# luxer.net
KiCad netlist of a schematic drawn in EasyEDA
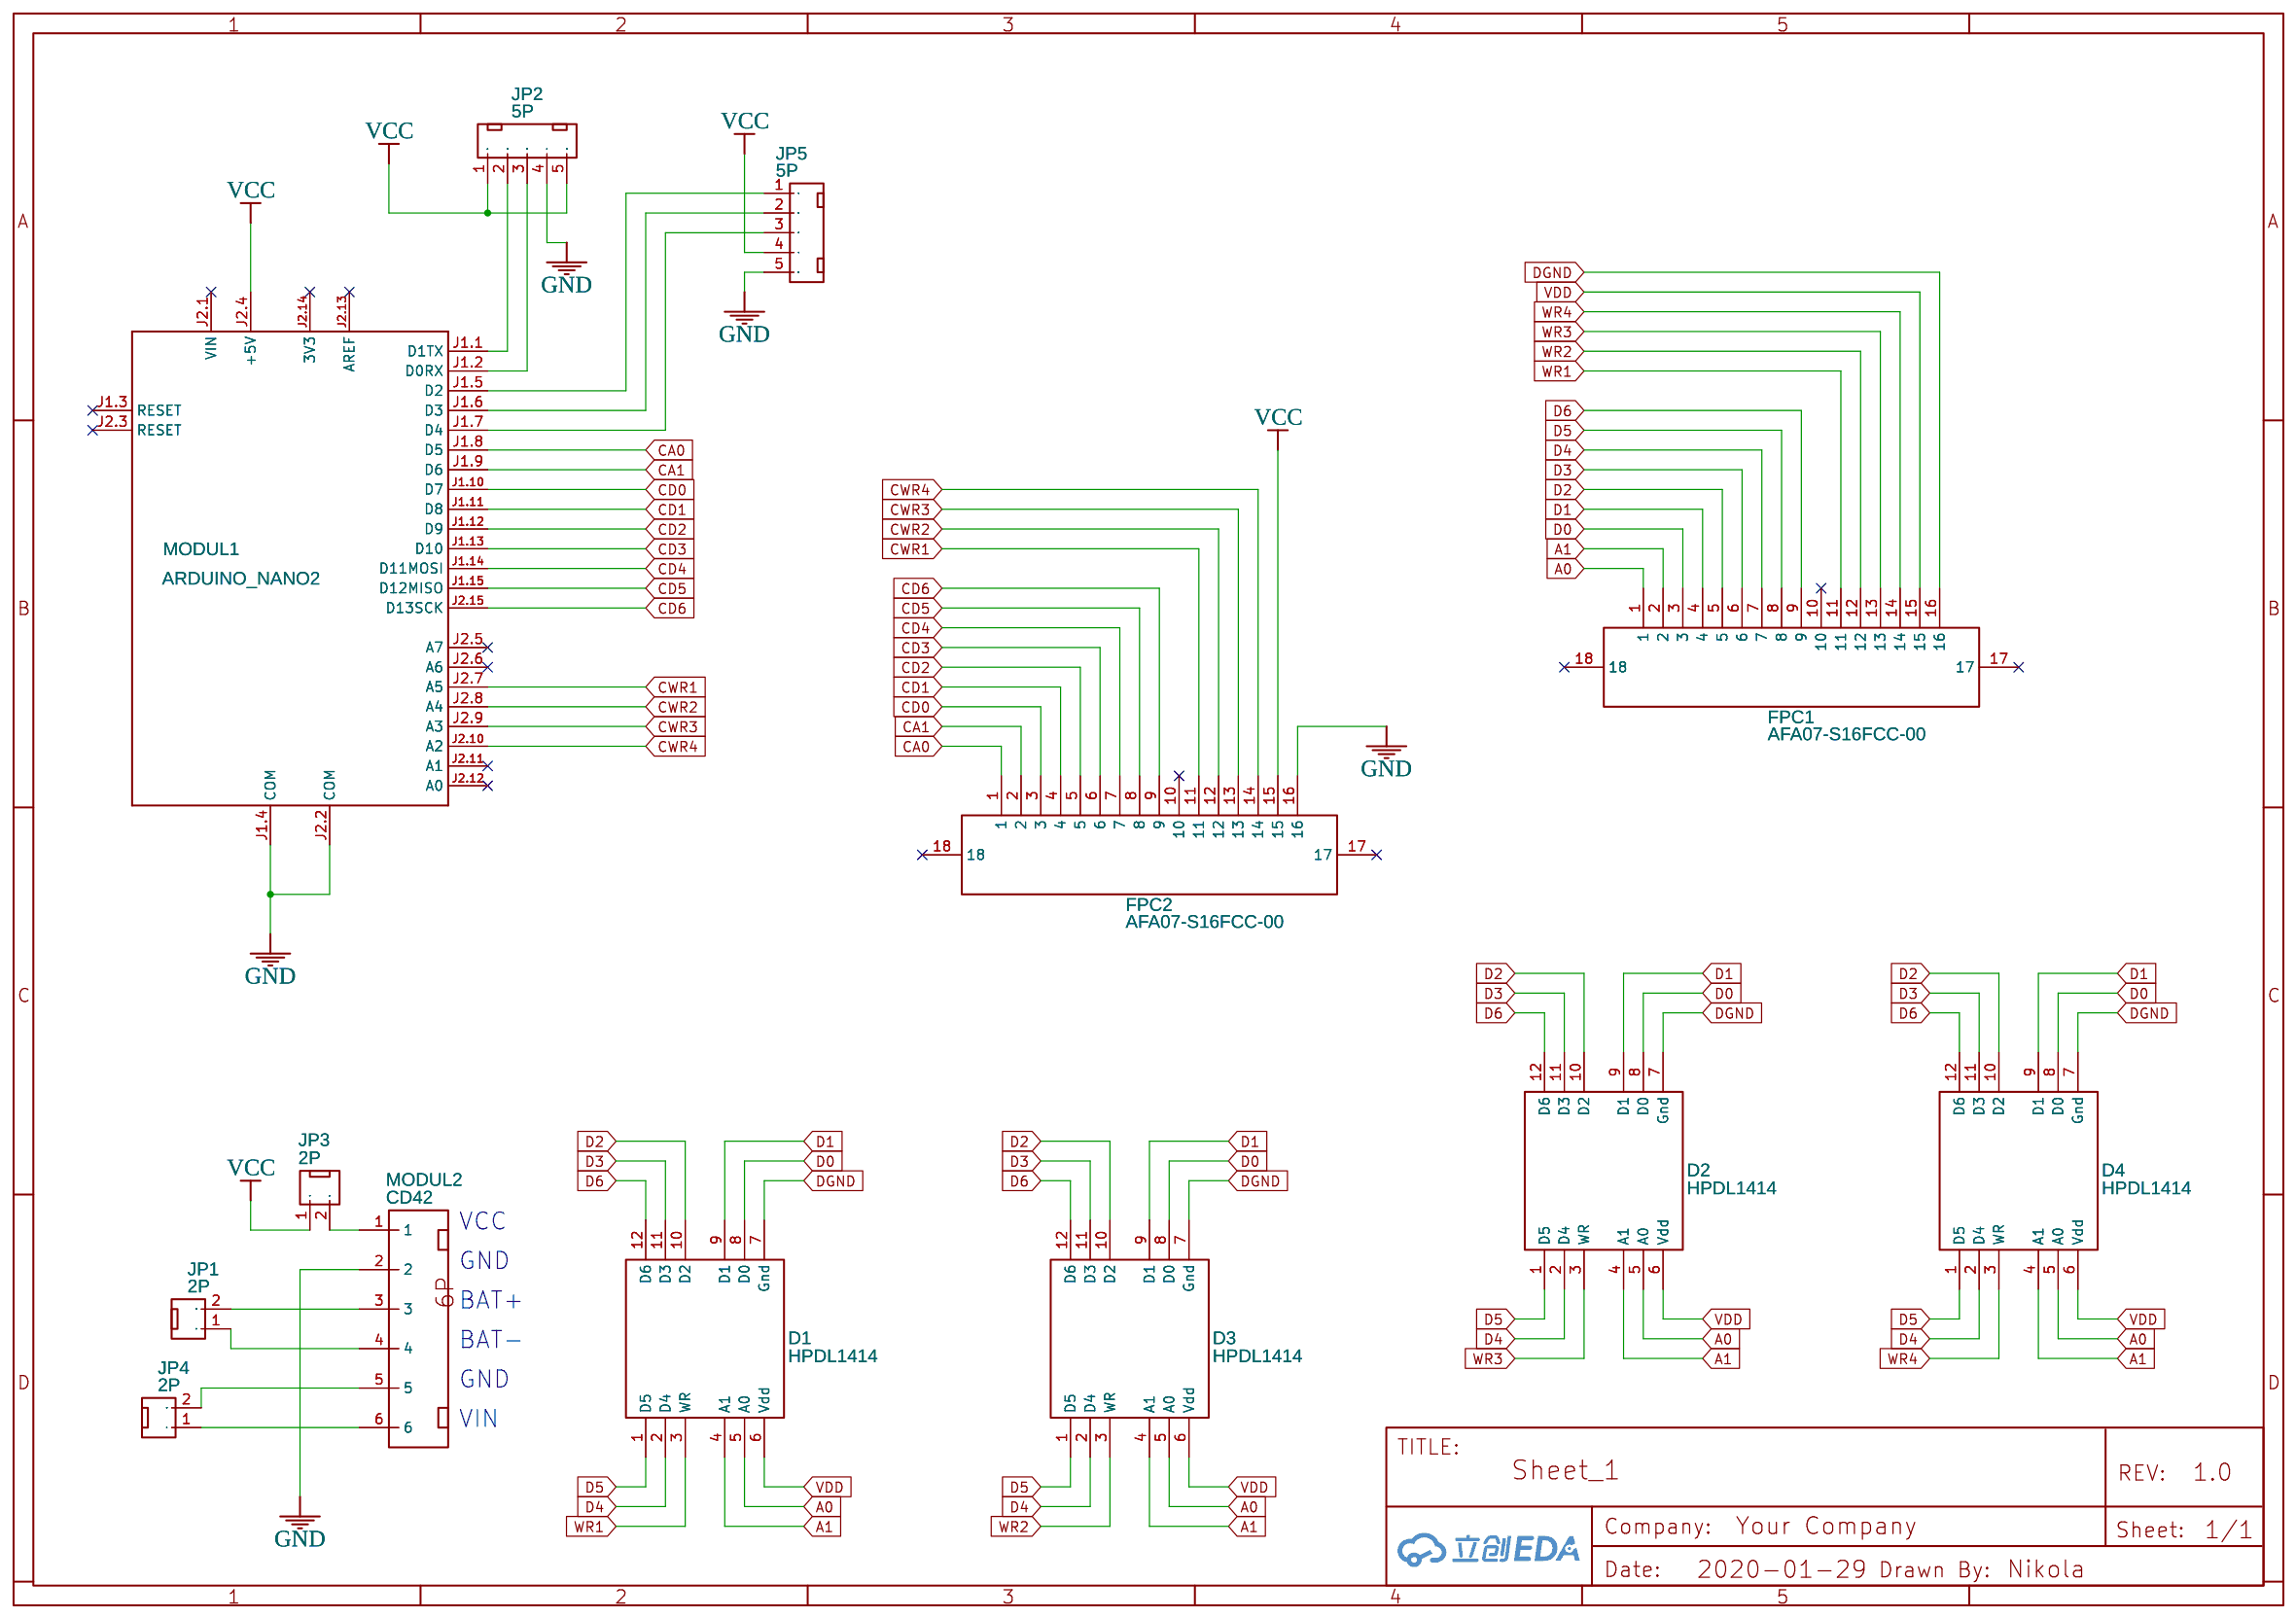
[diagram p0: schematic sheet]

(export (version "E")
  (design (tool "Eeschema 10.0.6"))
  (components
    (comp (ref "D1") (value "HPDL1414") (libsource (lib "") (part "HPDL1414")))
    (comp (ref "D2") (value "HPDL1414") (libsource (lib "") (part "HPDL1414")))
    (comp (ref "D3") (value "HPDL1414") (libsource (lib "") (part "HPDL1414")))
    (comp (ref "D4") (value "HPDL1414") (libsource (lib "") (part "HPDL1414")))
    (comp (ref "FPC1")
      (value "AFA07-S16FCC-00")
      (fields (field (name "BOM_Supplier Part") "C13744"))
      (libsource (lib "") (part "AFA07-S16FCC-00"))
    )
    (comp (ref "FPC2")
      (value "AFA07-S16FCC-00")
      (fields (field (name "BOM_Supplier Part") "C13744"))
      (libsource (lib "") (part "AFA07-S16FCC-00"))
    )
    (comp (ref "JP1")
      (value "2P")
      (fields (field (name "BOM_Supplier Part") "undefined"))
      (libsource (lib "") (part "2P"))
    )
    (comp (ref "JP2")
      (value "5P")
      (fields (field (name "BOM_Supplier Part") "undefined"))
      (libsource (lib "") (part "5P_1"))
    )
    (comp (ref "JP3")
      (value "2P")
      (fields (field (name "BOM_Supplier Part") "undefined"))
      (libsource (lib "") (part "2P_1"))
    )
    (comp (ref "JP4")
      (value "2P")
      (fields (field (name "BOM_Supplier Part") "undefined"))
      (libsource (lib "") (part "2P"))
    )
    (comp (ref "JP5")
      (value "5P")
      (fields (field (name "BOM_Supplier Part") "undefined"))
      (libsource (lib "") (part "5P"))
    )
    (comp (ref "MODUL1") (value "ARDUINO_NANO2") (libsource (lib "") (part "ARDUINO_NANO2")))
    (comp (ref "MODUL2")
      (value "CD42")
      (fields (field (name "BOM_Supplier Part") "undefined"))
      (libsource (lib "") (part "6P"))
    )
  )
  (nets
    (net (code "1") (name "A0") (class "Default")
      (node (ref "D1") (pin "5") (pinfunction "A0_5") (pintype "unspecified"))
      (node (ref "D2") (pin "5") (pinfunction "A0_5") (pintype "unspecified"))
      (node (ref "D3") (pin "5") (pinfunction "A0_5") (pintype "unspecified"))
      (node (ref "D4") (pin "5") (pinfunction "A0_5") (pintype "unspecified"))
      (node (ref "FPC1") (pin "1") (pinfunction "1_1") (pintype "unspecified"))
    )
    (net (code "2") (name "A1") (class "Default")
      (node (ref "D1") (pin "4") (pinfunction "A1_4") (pintype "unspecified"))
      (node (ref "D2") (pin "4") (pinfunction "A1_4") (pintype "unspecified"))
      (node (ref "D3") (pin "4") (pinfunction "A1_4") (pintype "unspecified"))
      (node (ref "D4") (pin "4") (pinfunction "A1_4") (pintype "unspecified"))
      (node (ref "FPC1") (pin "2") (pinfunction "2_2") (pintype "unspecified"))
    )
    (net (code "3") (name "CA0") (class "Default")
      (node (ref "FPC2") (pin "1") (pinfunction "1_1") (pintype "unspecified"))
      (node (ref "MODUL1") (pin "J1.8") (pinfunction "D5_J1.8") (pintype "unspecified"))
    )
    (net (code "4") (name "CA1") (class "Default")
      (node (ref "FPC2") (pin "2") (pinfunction "2_2") (pintype "unspecified"))
      (node (ref "MODUL1") (pin "J1.9") (pinfunction "D6_J1.9") (pintype "unspecified"))
    )
    (net (code "5") (name "CD0") (class "Default")
      (node (ref "FPC2") (pin "3") (pinfunction "3_3") (pintype "unspecified"))
      (node (ref "MODUL1") (pin "J1.10") (pinfunction "D7_J1.10") (pintype "unspecified"))
    )
    (net (code "6") (name "CD1") (class "Default")
      (node (ref "FPC2") (pin "4") (pinfunction "4_4") (pintype "unspecified"))
      (node (ref "MODUL1") (pin "J1.11") (pinfunction "D8_J1.11") (pintype "unspecified"))
    )
    (net (code "7") (name "CD2") (class "Default")
      (node (ref "FPC2") (pin "5") (pinfunction "5_5") (pintype "unspecified"))
      (node (ref "MODUL1") (pin "J1.12") (pinfunction "D9_J1.12") (pintype "unspecified"))
    )
    (net (code "8") (name "CD3") (class "Default")
      (node (ref "FPC2") (pin "6") (pinfunction "6_6") (pintype "unspecified"))
      (node (ref "MODUL1") (pin "J1.13") (pinfunction "D10_J1.13") (pintype "unspecified"))
    )
    (net (code "9") (name "CD4") (class "Default")
      (node (ref "FPC2") (pin "7") (pinfunction "7_7") (pintype "unspecified"))
      (node (ref "MODUL1") (pin "J1.14") (pinfunction "D11MOSI_J1.14") (pintype "unspecified"))
    )
    (net (code "10") (name "CD5") (class "Default")
      (node (ref "FPC2") (pin "8") (pinfunction "8_8") (pintype "unspecified"))
      (node (ref "MODUL1") (pin "J1.15") (pinfunction "D12MISO_J1.15") (pintype "unspecified"))
    )
    (net (code "11") (name "CD6") (class "Default")
      (node (ref "FPC2") (pin "9") (pinfunction "9_9") (pintype "unspecified"))
      (node (ref "MODUL1") (pin "J2.15") (pinfunction "D13SCK_J2.15") (pintype "unspecified"))
    )
    (net (code "12") (name "CWR1") (class "Default")
      (node (ref "FPC2") (pin "11") (pinfunction "11_11") (pintype "unspecified"))
      (node (ref "MODUL1") (pin "J2.7") (pinfunction "A5_J2.7") (pintype "unspecified"))
    )
    (net (code "13") (name "CWR2") (class "Default")
      (node (ref "FPC2") (pin "12") (pinfunction "12_12") (pintype "unspecified"))
      (node (ref "MODUL1") (pin "J2.8") (pinfunction "A4_J2.8") (pintype "unspecified"))
    )
    (net (code "14") (name "CWR3") (class "Default")
      (node (ref "FPC2") (pin "13") (pinfunction "13_13") (pintype "unspecified"))
      (node (ref "MODUL1") (pin "J2.9") (pinfunction "A3_J2.9") (pintype "unspecified"))
    )
    (net (code "15") (name "CWR4") (class "Default")
      (node (ref "FPC2") (pin "14") (pinfunction "14_14") (pintype "unspecified"))
      (node (ref "MODUL1") (pin "J2.10") (pinfunction "A2_J2.10") (pintype "unspecified"))
    )
    (net (code "16") (name "D0") (class "Default")
      (node (ref "D1") (pin "8") (pinfunction "D0_8") (pintype "unspecified"))
      (node (ref "D2") (pin "8") (pinfunction "D0_8") (pintype "unspecified"))
      (node (ref "D3") (pin "8") (pinfunction "D0_8") (pintype "unspecified"))
      (node (ref "D4") (pin "8") (pinfunction "D0_8") (pintype "unspecified"))
      (node (ref "FPC1") (pin "3") (pinfunction "3_3") (pintype "unspecified"))
    )
    (net (code "17") (name "D1") (class "Default")
      (node (ref "D1") (pin "9") (pinfunction "D1_9") (pintype "unspecified"))
      (node (ref "D2") (pin "9") (pinfunction "D1_9") (pintype "unspecified"))
      (node (ref "D3") (pin "9") (pinfunction "D1_9") (pintype "unspecified"))
      (node (ref "D4") (pin "9") (pinfunction "D1_9") (pintype "unspecified"))
      (node (ref "FPC1") (pin "4") (pinfunction "4_4") (pintype "unspecified"))
    )
    (net (code "18") (name "D2") (class "Default")
      (node (ref "D1") (pin "10") (pinfunction "D2_10") (pintype "unspecified"))
      (node (ref "D2") (pin "10") (pinfunction "D2_10") (pintype "unspecified"))
      (node (ref "D3") (pin "10") (pinfunction "D2_10") (pintype "unspecified"))
      (node (ref "D4") (pin "10") (pinfunction "D2_10") (pintype "unspecified"))
      (node (ref "FPC1") (pin "5") (pinfunction "5_5") (pintype "unspecified"))
    )
    (net (code "19") (name "D3") (class "Default")
      (node (ref "D1") (pin "11") (pinfunction "D3_11") (pintype "unspecified"))
      (node (ref "D2") (pin "11") (pinfunction "D3_11") (pintype "unspecified"))
      (node (ref "D3") (pin "11") (pinfunction "D3_11") (pintype "unspecified"))
      (node (ref "D4") (pin "11") (pinfunction "D3_11") (pintype "unspecified"))
      (node (ref "FPC1") (pin "6") (pinfunction "6_6") (pintype "unspecified"))
    )
    (net (code "20") (name "D4") (class "Default")
      (node (ref "D1") (pin "2") (pinfunction "D4_2") (pintype "unspecified"))
      (node (ref "D2") (pin "2") (pinfunction "D4_2") (pintype "unspecified"))
      (node (ref "D3") (pin "2") (pinfunction "D4_2") (pintype "unspecified"))
      (node (ref "D4") (pin "2") (pinfunction "D4_2") (pintype "unspecified"))
      (node (ref "FPC1") (pin "7") (pinfunction "7_7") (pintype "unspecified"))
    )
    (net (code "21") (name "D5") (class "Default")
      (node (ref "D1") (pin "1") (pinfunction "D5_1") (pintype "unspecified"))
      (node (ref "D2") (pin "1") (pinfunction "D5_1") (pintype "unspecified"))
      (node (ref "D3") (pin "1") (pinfunction "D5_1") (pintype "unspecified"))
      (node (ref "D4") (pin "1") (pinfunction "D5_1") (pintype "unspecified"))
      (node (ref "FPC1") (pin "8") (pinfunction "8_8") (pintype "unspecified"))
    )
    (net (code "22") (name "D6") (class "Default")
      (node (ref "D1") (pin "12") (pinfunction "D6_12") (pintype "unspecified"))
      (node (ref "D2") (pin "12") (pinfunction "D6_12") (pintype "unspecified"))
      (node (ref "D3") (pin "12") (pinfunction "D6_12") (pintype "unspecified"))
      (node (ref "D4") (pin "12") (pinfunction "D6_12") (pintype "unspecified"))
      (node (ref "FPC1") (pin "9") (pinfunction "9_9") (pintype "unspecified"))
    )
    (net (code "23") (name "DGND") (class "Default")
      (node (ref "D1") (pin "7") (pinfunction "Gnd_7") (pintype "unspecified"))
      (node (ref "D2") (pin "7") (pinfunction "Gnd_7") (pintype "unspecified"))
      (node (ref "D3") (pin "7") (pinfunction "Gnd_7") (pintype "unspecified"))
      (node (ref "D4") (pin "7") (pinfunction "Gnd_7") (pintype "unspecified"))
      (node (ref "FPC1") (pin "16") (pinfunction "16_16") (pintype "unspecified"))
    )
    (net (code "24") (name "GND") (class "Default")
      (node (ref "FPC2") (pin "16") (pinfunction "16_16") (pintype "unspecified"))
      (node (ref "JP2") (pin "4") (pinfunction "4_4") (pintype "unspecified"))
      (node (ref "JP5") (pin "5") (pinfunction "5_5") (pintype "unspecified"))
      (node (ref "MODUL1") (pin "J1.4") (pinfunction "COM_J1.4") (pintype "passive"))
      (node (ref "MODUL1") (pin "J2.2") (pinfunction "COM_J2.2") (pintype "passive"))
      (node (ref "MODUL2") (pin "2") (pinfunction "2_2") (pintype "unspecified"))
    )
    (net (code "25") (name "Net-(JP1-Pad1)") (class "Default")
      (node (ref "JP1") (pin "1") (pinfunction "1_1") (pintype "unspecified"))
      (node (ref "MODUL2") (pin "4") (pinfunction "4_4") (pintype "unspecified"))
    )
    (net (code "26") (name "Net-(JP1-Pad2)") (class "Default")
      (node (ref "JP1") (pin "2") (pinfunction "2_2") (pintype "unspecified"))
      (node (ref "MODUL2") (pin "3") (pinfunction "3_3") (pintype "unspecified"))
    )
    (net (code "27") (name "Net-(JP3-Pad2)") (class "Default")
      (node (ref "JP3") (pin "2") (pinfunction "2_2") (pintype "unspecified"))
      (node (ref "MODUL2") (pin "1") (pinfunction "1_1") (pintype "unspecified"))
    )
    (net (code "28") (name "Net-(JP4-Pad1)") (class "Default")
      (node (ref "JP4") (pin "1") (pinfunction "1_1") (pintype "unspecified"))
      (node (ref "MODUL2") (pin "6") (pinfunction "6_6") (pintype "unspecified"))
    )
    (net (code "29") (name "Net-(JP4-Pad2)") (class "Default")
      (node (ref "JP4") (pin "2") (pinfunction "2_2") (pintype "unspecified"))
      (node (ref "MODUL2") (pin "5") (pinfunction "5_5") (pintype "unspecified"))
    )
    (net (code "30") (name "Net-(MODUL1-D0RX)") (class "Default")
      (node (ref "JP2") (pin "3") (pinfunction "3_3") (pintype "unspecified"))
      (node (ref "MODUL1") (pin "J1.2") (pinfunction "D0RX_J1.2") (pintype "unspecified"))
    )
    (net (code "31") (name "Net-(MODUL1-D1TX)") (class "Default")
      (node (ref "JP2") (pin "2") (pinfunction "2_2") (pintype "unspecified"))
      (node (ref "MODUL1") (pin "J1.1") (pinfunction "D1TX_J1.1") (pintype "unspecified"))
    )
    (net (code "32") (name "Net-(MODUL1-D2)") (class "Default")
      (node (ref "JP5") (pin "1") (pinfunction "1_1") (pintype "unspecified"))
      (node (ref "MODUL1") (pin "J1.5") (pinfunction "D2_J1.5") (pintype "unspecified"))
    )
    (net (code "33") (name "Net-(MODUL1-D3)") (class "Default")
      (node (ref "JP5") (pin "2") (pinfunction "2_2") (pintype "unspecified"))
      (node (ref "MODUL1") (pin "J1.6") (pinfunction "D3_J1.6") (pintype "unspecified"))
    )
    (net (code "34") (name "Net-(MODUL1-D4)") (class "Default")
      (node (ref "JP5") (pin "3") (pinfunction "3_3") (pintype "unspecified"))
      (node (ref "MODUL1") (pin "J1.7") (pinfunction "D4_J1.7") (pintype "unspecified"))
    )
    (net (code "35") (name "VCC") (class "Default")
      (node (ref "FPC2") (pin "15") (pinfunction "15_15") (pintype "unspecified"))
      (node (ref "JP2") (pin "1") (pinfunction "1_1") (pintype "unspecified"))
      (node (ref "JP2") (pin "5") (pinfunction "5_5") (pintype "unspecified"))
      (node (ref "JP3") (pin "1") (pinfunction "1_1") (pintype "unspecified"))
      (node (ref "JP5") (pin "4") (pinfunction "4_4") (pintype "unspecified"))
      (node (ref "MODUL1") (pin "J2.4") (pinfunction "+5V_J2.4") (pintype "passive"))
    )
    (net (code "36") (name "VDD") (class "Default")
      (node (ref "D1") (pin "6") (pinfunction "Vdd_6") (pintype "unspecified"))
      (node (ref "D2") (pin "6") (pinfunction "Vdd_6") (pintype "unspecified"))
      (node (ref "D3") (pin "6") (pinfunction "Vdd_6") (pintype "unspecified"))
      (node (ref "D4") (pin "6") (pinfunction "Vdd_6") (pintype "unspecified"))
      (node (ref "FPC1") (pin "15") (pinfunction "15_15") (pintype "unspecified"))
    )
    (net (code "37") (name "WR1") (class "Default")
      (node (ref "D1") (pin "3") (pinfunction "WR_3") (pintype "unspecified"))
      (node (ref "FPC1") (pin "11") (pinfunction "11_11") (pintype "unspecified"))
    )
    (net (code "38") (name "WR2") (class "Default")
      (node (ref "D3") (pin "3") (pinfunction "WR_3") (pintype "unspecified"))
      (node (ref "FPC1") (pin "12") (pinfunction "12_12") (pintype "unspecified"))
    )
    (net (code "39") (name "WR3") (class "Default")
      (node (ref "D2") (pin "3") (pinfunction "WR_3") (pintype "unspecified"))
      (node (ref "FPC1") (pin "13") (pinfunction "13_13") (pintype "unspecified"))
    )
    (net (code "40") (name "WR4") (class "Default")
      (node (ref "D4") (pin "3") (pinfunction "WR_3") (pintype "unspecified"))
      (node (ref "FPC1") (pin "14") (pinfunction "14_14") (pintype "unspecified"))
    )
    (net (code "41") (name "unconnected-(FPC1-Pad10)") (class "Default")
      (node (ref "FPC1") (pin "10") (pinfunction "10_10") (pintype "unspecified+no_connect"))
    )
    (net (code "42") (name "unconnected-(FPC1-Pad17)") (class "Default")
      (node (ref "FPC1") (pin "17") (pinfunction "17_17") (pintype "unspecified+no_connect"))
    )
    (net (code "43") (name "unconnected-(FPC1-Pad18)") (class "Default")
      (node (ref "FPC1") (pin "18") (pinfunction "18_18") (pintype "unspecified+no_connect"))
    )
    (net (code "44") (name "unconnected-(FPC2-Pad10)") (class "Default")
      (node (ref "FPC2") (pin "10") (pinfunction "10_10") (pintype "unspecified+no_connect"))
    )
    (net (code "45") (name "unconnected-(FPC2-Pad17)") (class "Default")
      (node (ref "FPC2") (pin "17") (pinfunction "17_17") (pintype "unspecified+no_connect"))
    )
    (net (code "46") (name "unconnected-(FPC2-Pad18)") (class "Default")
      (node (ref "FPC2") (pin "18") (pinfunction "18_18") (pintype "unspecified+no_connect"))
    )
    (net (code "47") (name "unconnected-(MODUL1-3V3-PadJ2.14)") (class "Default")
      (node (ref "MODUL1") (pin "J2.14") (pinfunction "3V3_J2.14") (pintype "passive+no_connect"))
    )
    (net (code "48") (name "unconnected-(MODUL1-A0-PadJ2.12)") (class "Default")
      (node (ref "MODUL1") (pin "J2.12") (pinfunction "A0_J2.12") (pintype "unspecified+no_connect"))
    )
    (net (code "49") (name "unconnected-(MODUL1-A1-PadJ2.11)") (class "Default")
      (node (ref "MODUL1") (pin "J2.11") (pinfunction "A1_J2.11") (pintype "unspecified+no_connect"))
    )
    (net (code "50") (name "unconnected-(MODUL1-A6-PadJ2.6)") (class "Default")
      (node (ref "MODUL1") (pin "J2.6") (pinfunction "A6_J2.6") (pintype "unspecified+no_connect"))
    )
    (net (code "51") (name "unconnected-(MODUL1-A7-PadJ2.5)") (class "Default")
      (node (ref "MODUL1") (pin "J2.5") (pinfunction "A7_J2.5") (pintype "unspecified+no_connect"))
    )
    (net (code "52") (name "unconnected-(MODUL1-AREF-PadJ2.13)") (class "Default")
      (node (ref "MODUL1") (pin "J2.13") (pinfunction "AREF_J2.13") (pintype "passive+no_connect"))
    )
    (net (code "53") (name "unconnected-(MODUL1-RESET-PadJ1.3)") (class "Default")
      (node (ref "MODUL1") (pin "J1.3") (pinfunction "RESET_J1.3") (pintype "unspecified+no_connect"))
    )
    (net (code "54") (name "unconnected-(MODUL1-RESET-PadJ2.3)") (class "Default")
      (node (ref "MODUL1") (pin "J2.3") (pinfunction "RESET_J2.3") (pintype "unspecified+no_connect"))
    )
    (net (code "55") (name "unconnected-(MODUL1-VIN-PadJ2.1)") (class "Default")
      (node (ref "MODUL1") (pin "J2.1") (pinfunction "VIN_J2.1") (pintype "passive+no_connect"))
    )
  )
)
